# Fume_Extractor.net
KiCad netlist of a schematic drawn in EAGLE
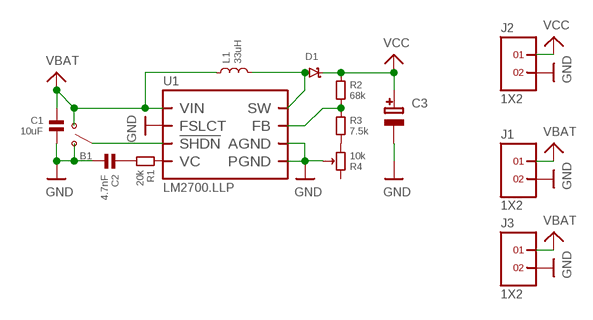
[diagram p0: schematic, sheet 1]

(export (version "E")
  (design (tool "Eeschema 10.0.6"))
  (components
    (comp (ref "B1")
      (value "SSSS810701")
      (footprint "eagle-import:SSSS810701")
      (libsource (lib "eagle-import") (part "SSSS810701"))
    )
    (comp (ref "C1")
      (value "10uF")
      (footprint "eagle-import:0805")
      (libsource (lib "eagle-import") (part "CAPACITOR.0805"))
    )
    (comp (ref "C2")
      (value "4.7nF")
      (footprint "eagle-import:0603")
      (libsource (lib "eagle-import") (part "CAPACITOR.0603"))
    )
    (comp (ref "C3")
      (value "CAP_ELECTROLYTICPANASONIC_D")
      (footprint "eagle-import:PANASONIC_D")
      (libsource (lib "eagle-import") (part "CAP_ELECTROLYTICPANASONIC_D"))
    )
    (comp (ref "D1")
      (value "DIODE[SCHOTKY]-SOD123W")
      (footprint "eagle-import:SOD123W")
      (libsource (lib "eagle-import") (part "DIODE[SCHOTKY]-SOD123W"))
    )
    (comp (ref "J1")
      (value "1X2")
      (footprint "eagle-import:1X2")
      (libsource (lib "eagle-import") (part "1X2"))
    )
    (comp (ref "J2")
      (value "1X2")
      (footprint "eagle-import:1X2")
      (libsource (lib "eagle-import") (part "1X2"))
    )
    (comp (ref "J3")
      (value "1X2")
      (footprint "eagle-import:1X2")
      (libsource (lib "eagle-import") (part "1X2"))
    )
    (comp (ref "L1")
      (value "33uH")
      (footprint "eagle-import:SRN6045")
      (libsource (lib "eagle-import") (part "INDUCTOR-SRN6045"))
    )
    (comp (ref "R1")
      (value "20k")
      (footprint "eagle-import:0603")
      (libsource (lib "eagle-import") (part "RESISTOR.0603"))
    )
    (comp (ref "R2")
      (value "68k")
      (footprint "eagle-import:0603")
      (libsource (lib "eagle-import") (part "RESISTOR.0603"))
    )
    (comp (ref "R3")
      (value "7.5k")
      (footprint "eagle-import:0603")
      (libsource (lib "eagle-import") (part "RESISTOR.0603"))
    )
    (comp (ref "R4")
      (value "10k")
      (footprint "eagle-import:RS08U111Z001")
      (libsource (lib "eagle-import") (part "RS08U111Z001"))
    )
    (comp (ref "U1")
      (value "LM2700.LLP")
      (footprint "eagle-import:LLP-EP")
      (libsource (lib "eagle-import") (part "LM2700.LLP"))
    )
  )
  (nets
    (net (code "1") (name "GND") (class "Default")
      (node (ref "B1") (pin "3") (pinfunction "A_3") (pintype "bidirectional"))
      (node (ref "C1") (pin "2") (pinfunction "2_2") (pintype "bidirectional"))
      (node (ref "C2") (pin "2") (pinfunction "2_2") (pintype "bidirectional"))
      (node (ref "C3") (pin "-") (pinfunction "-_-") (pintype "passive"))
      (node (ref "J1") (pin "2") (pinfunction "2_2") (pintype "bidirectional"))
      (node (ref "J2") (pin "2") (pinfunction "2_2") (pintype "bidirectional"))
      (node (ref "J3") (pin "2") (pinfunction "2_2") (pintype "bidirectional"))
      (node (ref "R4") (pin "B") (pinfunction "B_B") (pintype "bidirectional"))
      (node (ref "U1") (pin "13") (pinfunction "FSLCT_13") (pintype "bidirectional"))
      (node (ref "U1") (pin "4") (pinfunction "AGND_4") (pintype "bidirectional"))
      (node (ref "U1") (pin "5") (pinfunction "PGND_5") (pintype "bidirectional"))
      (node (ref "U1") (pin "6") (pinfunction "PGND_6") (pintype "bidirectional"))
      (node (ref "U1") (pin "7") (pinfunction "PGND_7") (pintype "bidirectional"))
      (node (ref "U1") (pin "PAD") (pinfunction "PGND_PAD") (pintype "bidirectional"))
    )
    (net (code "2") (name "Net-(B1-COM)") (class "Default")
      (node (ref "B1") (pin "2") (pinfunction "COM_2") (pintype "bidirectional"))
      (node (ref "U1") (pin "3") (pinfunction "~{SHDN}_3") (pintype "bidirectional"))
    )
    (net (code "3") (name "Net-(C2-Pad1)") (class "Default")
      (node (ref "C2") (pin "1") (pinfunction "1_1") (pintype "bidirectional"))
      (node (ref "R1") (pin "2") (pinfunction "2_2") (pintype "bidirectional"))
    )
    (net (code "4") (name "Net-(D1-1)") (class "Default")
      (node (ref "D1") (pin "P$1") (pinfunction "1_P$1") (pintype "bidirectional"))
      (node (ref "L1") (pin "2") (pinfunction "2_2") (pintype "passive"))
      (node (ref "U1") (pin "10") (pinfunction "SW_10") (pintype "bidirectional"))
      (node (ref "U1") (pin "8") (pinfunction "SW_8") (pintype "bidirectional"))
      (node (ref "U1") (pin "9") (pinfunction "SW_9") (pintype "bidirectional"))
    )
    (net (code "5") (name "Net-(R3-Pad2)") (class "Default")
      (node (ref "R3") (pin "2") (pinfunction "2_2") (pintype "bidirectional"))
      (node (ref "R4") (pin "C") (pinfunction "C_C") (pintype "bidirectional"))
    )
    (net (code "6") (name "Net-(U1-FB)") (class "Default")
      (node (ref "R2") (pin "2") (pinfunction "2_2") (pintype "bidirectional"))
      (node (ref "R3") (pin "1") (pinfunction "1_1") (pintype "bidirectional"))
      (node (ref "U1") (pin "2") (pinfunction "FB_2") (pintype "bidirectional"))
    )
    (net (code "7") (name "Net-(U1-VC)") (class "Default")
      (node (ref "R1") (pin "1") (pinfunction "1_1") (pintype "bidirectional"))
      (node (ref "U1") (pin "1") (pinfunction "VC_1") (pintype "bidirectional"))
    )
    (net (code "8") (name "VBAT") (class "Default")
      (node (ref "B1") (pin "1") (pinfunction "B_1") (pintype "bidirectional"))
      (node (ref "C1") (pin "1") (pinfunction "1_1") (pintype "bidirectional"))
      (node (ref "J1") (pin "1") (pinfunction "1_1") (pintype "bidirectional"))
      (node (ref "J3") (pin "1") (pinfunction "1_1") (pintype "bidirectional"))
      (node (ref "L1") (pin "1") (pinfunction "1_1") (pintype "passive"))
      (node (ref "U1") (pin "12") (pinfunction "VIN_12") (pintype "bidirectional"))
    )
    (net (code "9") (name "VCC") (class "Default")
      (node (ref "C3") (pin "+") (pinfunction "+_+") (pintype "passive"))
      (node (ref "D1") (pin "P$2") (pinfunction "2_P$2") (pintype "bidirectional"))
      (node (ref "J2") (pin "1") (pinfunction "1_1") (pintype "bidirectional"))
      (node (ref "R2") (pin "1") (pinfunction "1_1") (pintype "bidirectional"))
    )
    (net (code "10") (name "unconnected-(R4-PadA)") (class "Default")
      (node (ref "R4") (pin "A") (pinfunction "A_A") (pintype "bidirectional"))
    )
  )
)
